# MCU_Supply.net
KiCad netlist of a schematic drawn in Altium Designer
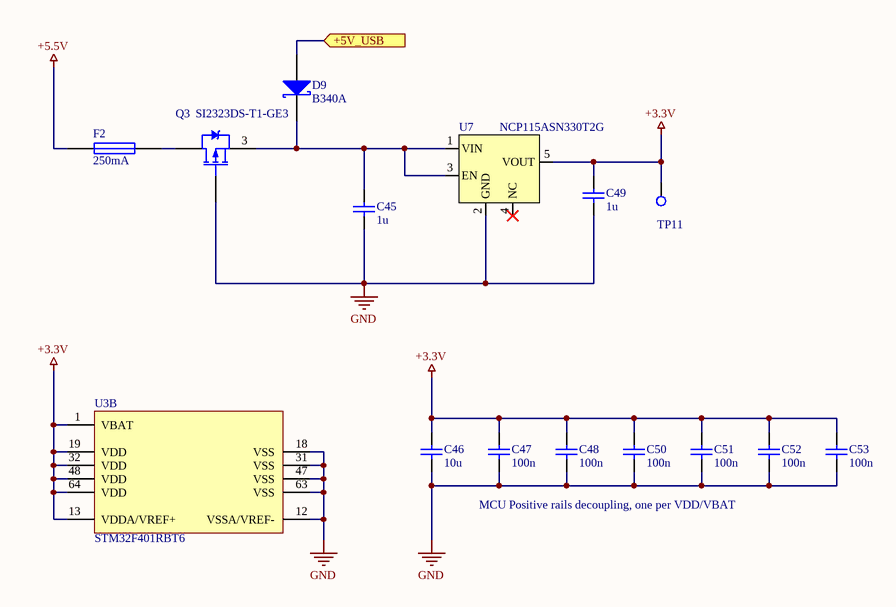
[diagram p0: MCU_Supply.SchDoc]

(export (version "E")
  (design (tool "Eeschema 10.0.6"))
  (components
    (comp (ref "C45")
      (value "1u")
      (footprint "CAPC1608X87N")
      (libsource (lib "Miscellaneous Devices") (part "Cap"))
    )
    (comp (ref "C46")
      (value "10u")
      (footprint "CAPC2012X110N")
      (libsource (lib "Miscellaneous Devices") (part "Cap"))
    )
    (comp (ref "C47")
      (value "100n")
      (footprint "CAPC1608X87N")
      (libsource (lib "Miscellaneous Devices") (part "Cap"))
    )
    (comp (ref "C48")
      (value "100n")
      (footprint "CAPC1608X87N")
      (libsource (lib "Miscellaneous Devices") (part "Cap"))
    )
    (comp (ref "C49")
      (value "1u")
      (footprint "CAPC1608X87N")
      (libsource (lib "Miscellaneous Devices") (part "Cap"))
    )
    (comp (ref "C50")
      (value "100n")
      (footprint "CAPC1608X87N")
      (libsource (lib "Miscellaneous Devices") (part "Cap"))
    )
    (comp (ref "C51")
      (value "100n")
      (footprint "CAPC1608X87N")
      (libsource (lib "Miscellaneous Devices") (part "Cap"))
    )
    (comp (ref "C52")
      (value "100n")
      (footprint "CAPC1608X87N")
      (libsource (lib "Miscellaneous Devices") (part "Cap"))
    )
    (comp (ref "C53")
      (value "100n")
      (footprint "CAPC1608X87N")
      (libsource (lib "Miscellaneous Devices") (part "Cap"))
    )
    (comp (ref "D9")
      (value "B340A")
      (footprint "SODFL5226X110N")
      (libsource (lib "Miscellaneous Devices") (part "D Schottky"))
    )
    (comp (ref "F2")
      (value "250mA")
      (footprint "RESC1608X55N")
      (libsource (lib "Miscellaneous Devices") (part "Fuse 1"))
    )
    (comp (ref "Q3")
      (value "SI2323DS-T1-GE3")
      (footprint "SOT95P237X112-3N")
      (libsource (lib "Miscellaneous Devices") (part "PMOS-2"))
    )
    (comp (ref "TP11")
      (value "TP")
      (footprint "TEST-POINT")
      (description "Generic test point")
      (libsource (lib "Custom_Lib") (part "TEST_POINT"))
    )
    (comp (ref "U3")
      (value "STM32F401RBT6")
      (footprint "QFP50P1200X1200X160-64N")
      (libsource (lib "STMicroelectronics STM32 F4") (part "STM32F401RBT6"))
    )
    (comp (ref "U7")
      (value "NCP115ASN330T2G")
      (footprint "SOT95P280X145-5N")
      (libsource (lib "Custom_Lib") (part "NCP115"))
    )
  )
  (nets
    (net (code "1") (name "+3.3V") (class "Default")
      (node (ref "C46") (pin "2") (pinfunction "2_2") (pintype "passive"))
      (node (ref "C47") (pin "1") (pinfunction "1_1") (pintype "passive"))
      (node (ref "C48") (pin "2") (pinfunction "2_2") (pintype "passive"))
      (node (ref "C49") (pin "2") (pinfunction "2_2") (pintype "passive"))
      (node (ref "C50") (pin "2") (pinfunction "2_2") (pintype "passive"))
      (node (ref "C51") (pin "2") (pinfunction "2_2") (pintype "passive"))
      (node (ref "C52") (pin "2") (pinfunction "2_2") (pintype "passive"))
      (node (ref "C53") (pin "2") (pinfunction "2_2") (pintype "passive"))
      (node (ref "TP11") (pin "0") (pinfunction "0_0") (pintype "passive"))
      (node (ref "U3") (pin "1") (pinfunction "VBAT_1") (pintype "power_in"))
      (node (ref "U3") (pin "13") (pinfunction "VDDA/VREF+_13") (pintype "power_in"))
      (node (ref "U3") (pin "19") (pinfunction "VDD_19") (pintype "power_in"))
      (node (ref "U3") (pin "32") (pinfunction "VDD_32") (pintype "power_in"))
      (node (ref "U3") (pin "48") (pinfunction "VDD_48") (pintype "power_in"))
      (node (ref "U3") (pin "64") (pinfunction "VDD_64") (pintype "power_in"))
      (node (ref "U7") (pin "5") (pinfunction "VOUT_5") (pintype "power_in"))
    )
    (net (code "2") (name "+5.5V") (class "Default")
      (node (ref "F2") (pin "1") (pinfunction "1_1") (pintype "passive"))
    )
    (net (code "3") (name "/+5V_USB") (class "Default")
      (node (ref "D9") (pin "1") (pinfunction "A_1") (pintype "passive"))
    )
    (net (code "4") (name "GND") (class "Default")
      (node (ref "C45") (pin "1") (pinfunction "1_1") (pintype "passive"))
      (node (ref "C46") (pin "1") (pinfunction "1_1") (pintype "passive"))
      (node (ref "C47") (pin "2") (pinfunction "2_2") (pintype "passive"))
      (node (ref "C48") (pin "1") (pinfunction "1_1") (pintype "passive"))
      (node (ref "C49") (pin "1") (pinfunction "1_1") (pintype "passive"))
      (node (ref "C50") (pin "1") (pinfunction "1_1") (pintype "passive"))
      (node (ref "C51") (pin "1") (pinfunction "1_1") (pintype "passive"))
      (node (ref "C52") (pin "1") (pinfunction "1_1") (pintype "passive"))
      (node (ref "C53") (pin "1") (pinfunction "1_1") (pintype "passive"))
      (node (ref "Q3") (pin "1") (pinfunction "G_1") (pintype "passive"))
      (node (ref "U3") (pin "12") (pinfunction "VSSA/VREF-_12") (pintype "power_in"))
      (node (ref "U3") (pin "18") (pinfunction "VSS_18") (pintype "power_in"))
      (node (ref "U3") (pin "31") (pinfunction "VSS_31") (pintype "power_in"))
      (node (ref "U3") (pin "47") (pinfunction "VSS_47") (pintype "power_in"))
      (node (ref "U3") (pin "63") (pinfunction "VSS_63") (pintype "power_in"))
      (node (ref "U7") (pin "2") (pinfunction "GND_2") (pintype "power_in"))
    )
    (net (code "5") (name "Net-(D9-K)") (class "Default")
      (node (ref "C45") (pin "2") (pinfunction "2_2") (pintype "passive"))
      (node (ref "D9") (pin "2") (pinfunction "K_2") (pintype "passive"))
      (node (ref "Q3") (pin "3") (pinfunction "S_3") (pintype "passive"))
      (node (ref "U7") (pin "1") (pinfunction "VIN_1") (pintype "power_in"))
      (node (ref "U7") (pin "3") (pinfunction "EN_3") (pintype "passive"))
    )
    (net (code "6") (name "Net-(Q3-D)") (class "Default")
      (node (ref "F2") (pin "2") (pinfunction "2_2") (pintype "passive"))
      (node (ref "Q3") (pin "2") (pinfunction "D_2") (pintype "passive"))
    )
    (net (code "7") (name "unconnected-(U7-NC-Pad4)") (class "Default")
      (node (ref "U7") (pin "4") (pinfunction "NC_4") (pintype "passive+no_connect"))
    )
  )
)
